# GyroCam_BNO055_v2.net
KiCad netlist of a schematic drawn in EAGLE
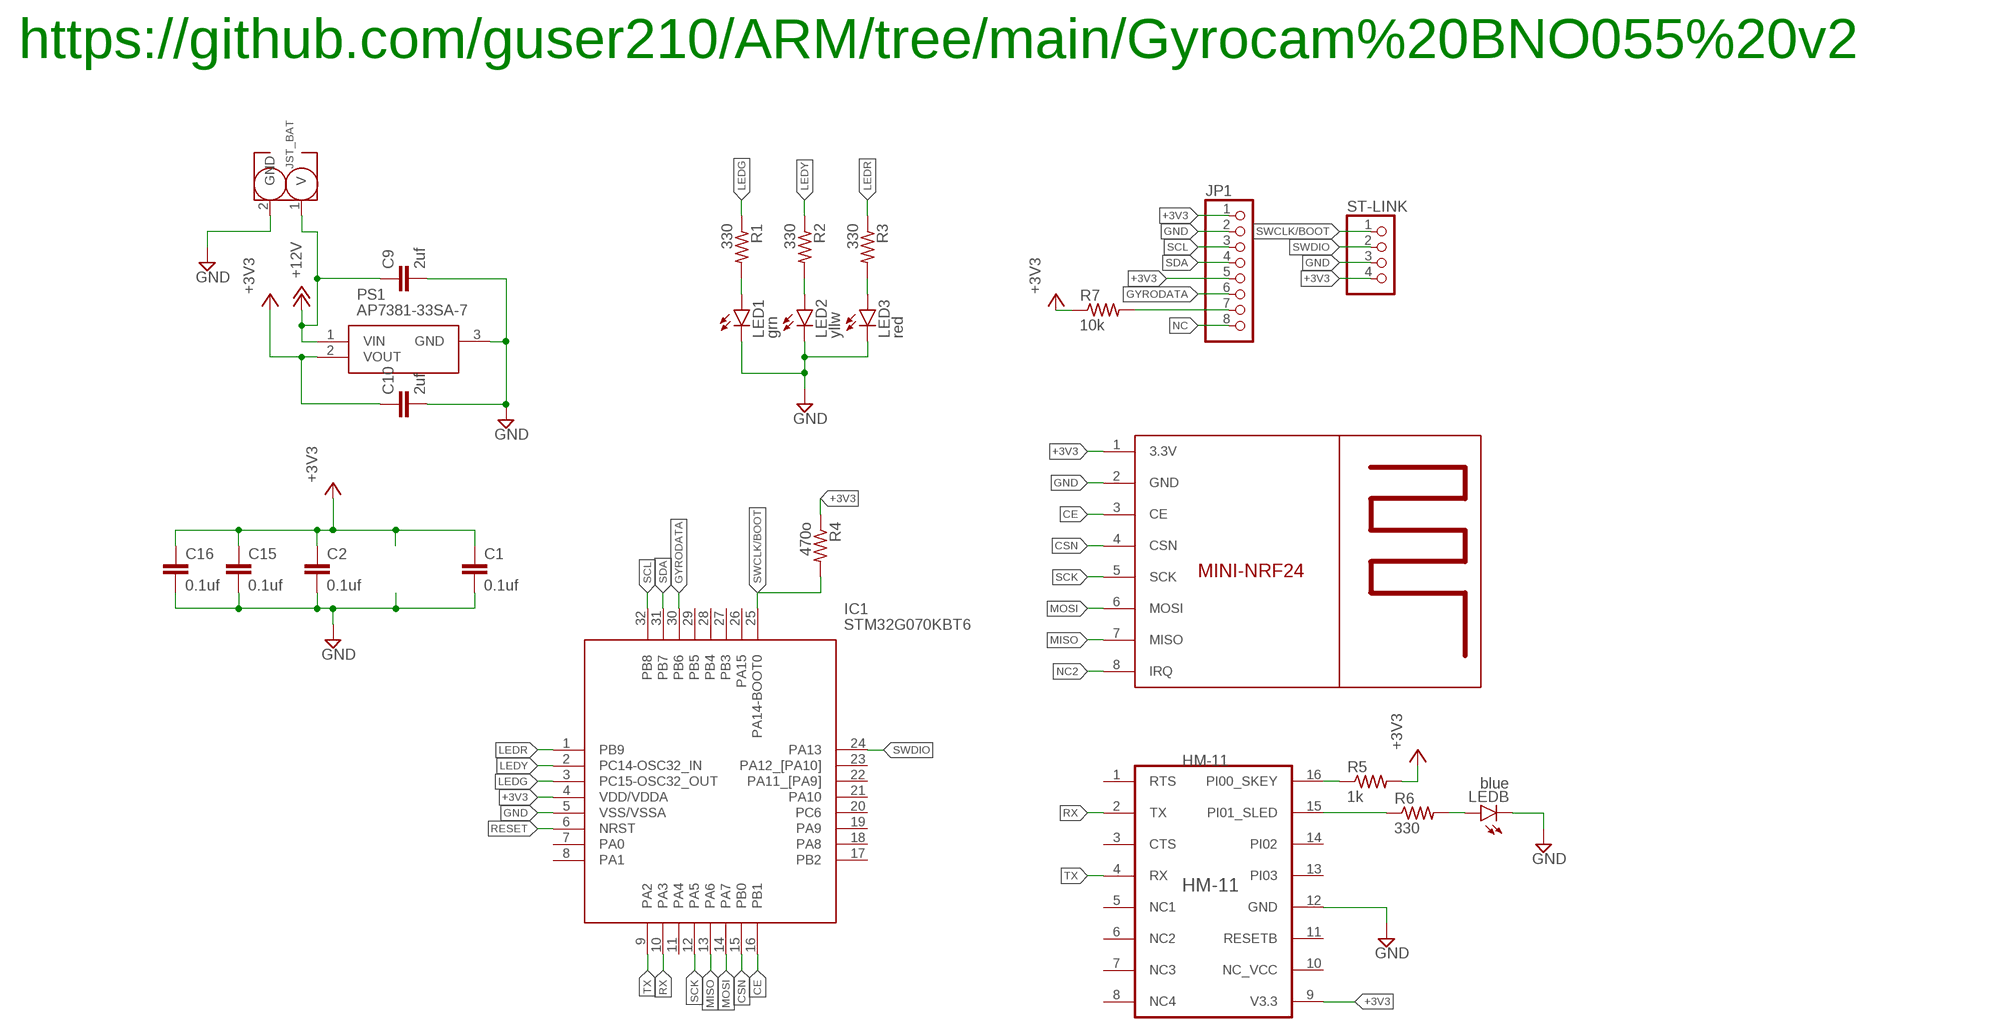
[diagram p0: schematic, sheet 1]

(export (version "E")
  (design (tool "Eeschema 10.0.6"))
  (components
    (comp (ref "C1")
      (value "0.1uf")
      (footprint "eagle-import:C0603K")
      (libsource (lib "eagle-import") (part "C-EUC0603K"))
    )
    (comp (ref "C2")
      (value "0.1uf")
      (footprint "eagle-import:C0805K")
      (libsource (lib "eagle-import") (part "C-EUC0805K"))
    )
    (comp (ref "C9")
      (value "2uf")
      (footprint "eagle-import:C0805K")
      (libsource (lib "eagle-import") (part "C-EUC0805K"))
    )
    (comp (ref "C10")
      (value "2uf")
      (footprint "eagle-import:C0805K")
      (libsource (lib "eagle-import") (part "C-EUC0805K"))
    )
    (comp (ref "C15")
      (value "0.1uf")
      (footprint "eagle-import:C0805K")
      (libsource (lib "eagle-import") (part "C-EUC0805K"))
    )
    (comp (ref "C16")
      (value "0.1uf")
      (footprint "eagle-import:C0805K")
      (libsource (lib "eagle-import") (part "C-EUC0805K"))
    )
    (comp (ref "IC1")
      (value "STM32G070KBT6")
      (footprint "eagle-import:QFP80P900X900X160-32N")
      (fields (field (name "MOUSER_PART_NUMBER") "511-STM32G070KBT6"))
      (libsource (lib "eagle-import") (part "STM32G070KBT6"))
    )
    (comp (ref "JP1")
      (value "PINHD-1X8")
      (footprint "eagle-import:1X08")
      (libsource (lib "eagle-import") (part "PINHD-1X8"))
    )
    (comp (ref "LED1")
      (value "grn")
      (footprint "eagle-import:SML0805")
      (libsource (lib "eagle-import") (part "LEDSML0805"))
    )
    (comp (ref "LED2")
      (value "yllw")
      (footprint "eagle-import:SML0805")
      (libsource (lib "eagle-import") (part "LEDSML0805"))
    )
    (comp (ref "LED3")
      (value "red")
      (footprint "eagle-import:SML0805")
      (libsource (lib "eagle-import") (part "LEDSML0805"))
    )
    (comp (ref "LEDB")
      (value "blue")
      (footprint "eagle-import:SML0805")
      (libsource (lib "eagle-import") (part "LEDSML0805"))
    )
    (comp (ref "PS1")
      (value "AP7381-33SA-7")
      (footprint "eagle-import:SOT96P240X120-3N")
      (fields (field (name "MOUSER_PART_NUMBER") "621-AP7381-33SA-7"))
      (libsource (lib "eagle-import") (part "AP7381-33SA-7"))
    )
    (comp (ref "R1")
      (value "330")
      (footprint "eagle-import:M0805")
      (libsource (lib "eagle-import") (part "R-US_M0805"))
    )
    (comp (ref "R2")
      (value "330")
      (footprint "eagle-import:M0805")
      (libsource (lib "eagle-import") (part "R-US_M0805"))
    )
    (comp (ref "R3")
      (value "330")
      (footprint "eagle-import:M0805")
      (libsource (lib "eagle-import") (part "R-US_M0805"))
    )
    (comp (ref "R4")
      (value "470o")
      (footprint "eagle-import:M0805")
      (libsource (lib "eagle-import") (part "R-US_M0805"))
    )
    (comp (ref "R5")
      (value "1k")
      (footprint "eagle-import:M0805")
      (libsource (lib "eagle-import") (part "R-US_M0805"))
    )
    (comp (ref "R6")
      (value "330")
      (footprint "eagle-import:M0805")
      (libsource (lib "eagle-import") (part "R-US_M0805"))
    )
    (comp (ref "R7")
      (value "10k")
      (footprint "eagle-import:M0805")
      (libsource (lib "eagle-import") (part "R-US_M0805"))
    )
    (comp (ref "ST-LINK")
      (value "PINHD-1X4")
      (footprint "eagle-import:1X04")
      (libsource (lib "eagle-import") (part "PINHD-1X4"))
    )
    (comp (ref "SUPP")
      (value "JST2.0MM_2PIN")
      (footprint "eagle-import:JST2.0MM_2PIN")
      (libsource (lib "eagle-import") (part "JST2.0MM_2PIN"))
    )
    (comp (ref "U$1")
      (value "HM-11")
      (footprint "eagle-import:HM-11")
      (libsource (lib "eagle-import") (part "HM-11"))
    )
    (comp (ref "U$3")
      (value "NRF24")
      (footprint "eagle-import:NRF24L01_SMD")
      (libsource (lib "eagle-import") (part "MINI-NRF24L01PSMD"))
    )
  )
  (nets
    (net (code "1") (name "+3V3") (class "Default")
      (node (ref "C1") (pin "1") (pinfunction "1_1") (pintype "passive"))
      (node (ref "C10") (pin "1") (pinfunction "1_1") (pintype "passive"))
      (node (ref "C15") (pin "1") (pinfunction "1_1") (pintype "passive"))
      (node (ref "C16") (pin "1") (pinfunction "1_1") (pintype "passive"))
      (node (ref "C2") (pin "1") (pinfunction "1_1") (pintype "passive"))
      (node (ref "IC1") (pin "4") (pinfunction "VDD/VDDA_4") (pintype "power_in"))
      (node (ref "JP1") (pin "1") (pinfunction "1_1") (pintype "passive"))
      (node (ref "JP1") (pin "5") (pinfunction "5_5") (pintype "passive"))
      (node (ref "PS1") (pin "2") (pinfunction "VOUT_2") (pintype "bidirectional"))
      (node (ref "R4") (pin "1") (pinfunction "1_1") (pintype "passive"))
      (node (ref "R5") (pin "2") (pinfunction "2_2") (pintype "passive"))
      (node (ref "R7") (pin "1") (pinfunction "1_1") (pintype "passive"))
      (node (ref "ST-LINK") (pin "4") (pinfunction "4_4") (pintype "passive"))
      (node (ref "U$1") (pin "9") (pinfunction "V3.3_9") (pintype "bidirectional"))
      (node (ref "U$3") (pin "1") (pinfunction "3.3V_1") (pintype "bidirectional"))
    )
    (net (code "2") (name "+12V") (class "Default")
      (node (ref "C9") (pin "1") (pinfunction "1_1") (pintype "passive"))
      (node (ref "PS1") (pin "1") (pinfunction "VIN_1") (pintype "bidirectional"))
      (node (ref "SUPP") (pin "1") (pinfunction "V_1") (pintype "power_in"))
    )
    (net (code "3") (name "CE") (class "Default")
      (node (ref "IC1") (pin "16") (pinfunction "PB1_16") (pintype "bidirectional"))
      (node (ref "U$3") (pin "3") (pinfunction "CE_3") (pintype "bidirectional"))
    )
    (net (code "4") (name "CSN") (class "Default")
      (node (ref "IC1") (pin "15") (pinfunction "PB0_15") (pintype "bidirectional"))
      (node (ref "U$3") (pin "4") (pinfunction "CSN_4") (pintype "bidirectional"))
    )
    (net (code "5") (name "GND") (class "Default")
      (node (ref "C1") (pin "2") (pinfunction "2_2") (pintype "passive"))
      (node (ref "C10") (pin "2") (pinfunction "2_2") (pintype "passive"))
      (node (ref "C15") (pin "2") (pinfunction "2_2") (pintype "passive"))
      (node (ref "C16") (pin "2") (pinfunction "2_2") (pintype "passive"))
      (node (ref "C2") (pin "2") (pinfunction "2_2") (pintype "passive"))
      (node (ref "C9") (pin "2") (pinfunction "2_2") (pintype "passive"))
      (node (ref "IC1") (pin "5") (pinfunction "VSS/VSSA_5") (pintype "power_in"))
      (node (ref "JP1") (pin "2") (pinfunction "2_2") (pintype "passive"))
      (node (ref "LED1") (pin "C") (pinfunction "C_C") (pintype "passive"))
      (node (ref "LED2") (pin "C") (pinfunction "C_C") (pintype "passive"))
      (node (ref "LED3") (pin "C") (pinfunction "C_C") (pintype "passive"))
      (node (ref "LEDB") (pin "C") (pinfunction "C_C") (pintype "passive"))
      (node (ref "PS1") (pin "3") (pinfunction "GND_3") (pintype "bidirectional"))
      (node (ref "ST-LINK") (pin "3") (pinfunction "3_3") (pintype "passive"))
      (node (ref "SUPP") (pin "2") (pinfunction "GND_2") (pintype "power_in"))
      (node (ref "U$1") (pin "12") (pinfunction "GND_12") (pintype "bidirectional"))
      (node (ref "U$3") (pin "2") (pinfunction "GND_2") (pintype "bidirectional"))
    )
    (net (code "6") (name "GYRODATA") (class "Default")
      (node (ref "IC1") (pin "30") (pinfunction "PB6_30") (pintype "bidirectional"))
      (node (ref "JP1") (pin "6") (pinfunction "6_6") (pintype "passive"))
    )
    (net (code "7") (name "LEDG") (class "Default")
      (node (ref "IC1") (pin "3") (pinfunction "PC15-OSC32_OUT_3") (pintype "bidirectional"))
      (node (ref "R1") (pin "1") (pinfunction "1_1") (pintype "passive"))
    )
    (net (code "8") (name "LEDR") (class "Default")
      (node (ref "IC1") (pin "1") (pinfunction "PB9_1") (pintype "bidirectional"))
      (node (ref "R3") (pin "1") (pinfunction "1_1") (pintype "passive"))
    )
    (net (code "9") (name "LEDY") (class "Default")
      (node (ref "IC1") (pin "2") (pinfunction "PC14-OSC32_IN_2") (pintype "bidirectional"))
      (node (ref "R2") (pin "1") (pinfunction "1_1") (pintype "passive"))
    )
    (net (code "10") (name "MISO") (class "Default")
      (node (ref "IC1") (pin "13") (pinfunction "PA6_13") (pintype "bidirectional"))
      (node (ref "U$3") (pin "7") (pinfunction "MISO_7") (pintype "bidirectional"))
    )
    (net (code "11") (name "MOSI") (class "Default")
      (node (ref "IC1") (pin "14") (pinfunction "PA7_14") (pintype "bidirectional"))
      (node (ref "U$3") (pin "6") (pinfunction "MOSI_6") (pintype "bidirectional"))
    )
    (net (code "12") (name "NC") (class "Default")
      (node (ref "JP1") (pin "8") (pinfunction "8_8") (pintype "passive"))
    )
    (net (code "13") (name "NC2") (class "Default")
      (node (ref "U$3") (pin "8") (pinfunction "IRQ_8") (pintype "bidirectional"))
    )
    (net (code "14") (name "Net-(JP1-Pad7)") (class "Default")
      (node (ref "JP1") (pin "7") (pinfunction "7_7") (pintype "passive"))
      (node (ref "R7") (pin "2") (pinfunction "2_2") (pintype "passive"))
    )
    (net (code "15") (name "Net-(LED1-PadA)") (class "Default")
      (node (ref "LED1") (pin "A") (pinfunction "A_A") (pintype "passive"))
      (node (ref "R1") (pin "2") (pinfunction "2_2") (pintype "passive"))
    )
    (net (code "16") (name "Net-(LED2-PadA)") (class "Default")
      (node (ref "LED2") (pin "A") (pinfunction "A_A") (pintype "passive"))
      (node (ref "R2") (pin "2") (pinfunction "2_2") (pintype "passive"))
    )
    (net (code "17") (name "Net-(LED3-PadA)") (class "Default")
      (node (ref "LED3") (pin "A") (pinfunction "A_A") (pintype "passive"))
      (node (ref "R3") (pin "2") (pinfunction "2_2") (pintype "passive"))
    )
    (net (code "18") (name "Net-(LEDB-PadA)") (class "Default")
      (node (ref "LEDB") (pin "A") (pinfunction "A_A") (pintype "passive"))
      (node (ref "R6") (pin "2") (pinfunction "2_2") (pintype "passive"))
    )
    (net (code "19") (name "Net-(U$1-PI00_SKEY)") (class "Default")
      (node (ref "R5") (pin "1") (pinfunction "1_1") (pintype "passive"))
      (node (ref "U$1") (pin "16") (pinfunction "PI00_SKEY_16") (pintype "bidirectional"))
    )
    (net (code "20") (name "Net-(U$1-PI01_SLED)") (class "Default")
      (node (ref "R6") (pin "1") (pinfunction "1_1") (pintype "passive"))
      (node (ref "U$1") (pin "15") (pinfunction "PI01_SLED_15") (pintype "bidirectional"))
    )
    (net (code "21") (name "RESET") (class "Default")
      (node (ref "IC1") (pin "6") (pinfunction "NRST_6") (pintype "bidirectional"))
    )
    (net (code "22") (name "RX") (class "Default")
      (node (ref "IC1") (pin "10") (pinfunction "PA3_10") (pintype "bidirectional"))
      (node (ref "U$1") (pin "2") (pinfunction "TX_2") (pintype "bidirectional"))
    )
    (net (code "23") (name "SCK") (class "Default")
      (node (ref "IC1") (pin "12") (pinfunction "PA5_12") (pintype "bidirectional"))
      (node (ref "U$3") (pin "5") (pinfunction "SCK_5") (pintype "bidirectional"))
    )
    (net (code "24") (name "SCL") (class "Default")
      (node (ref "IC1") (pin "32") (pinfunction "PB8_32") (pintype "bidirectional"))
      (node (ref "JP1") (pin "3") (pinfunction "3_3") (pintype "passive"))
    )
    (net (code "25") (name "SDA") (class "Default")
      (node (ref "IC1") (pin "31") (pinfunction "PB7_31") (pintype "bidirectional"))
      (node (ref "JP1") (pin "4") (pinfunction "4_4") (pintype "passive"))
    )
    (net (code "26") (name "SWCLK{slash}BOOT") (class "Default")
      (node (ref "IC1") (pin "25") (pinfunction "PA14-BOOT0_25") (pintype "bidirectional"))
      (node (ref "R4") (pin "2") (pinfunction "2_2") (pintype "passive"))
      (node (ref "ST-LINK") (pin "1") (pinfunction "1_1") (pintype "passive"))
    )
    (net (code "27") (name "SWDIO") (class "Default")
      (node (ref "IC1") (pin "24") (pinfunction "PA13_24") (pintype "bidirectional"))
      (node (ref "ST-LINK") (pin "2") (pinfunction "2_2") (pintype "passive"))
    )
    (net (code "28") (name "TX") (class "Default")
      (node (ref "IC1") (pin "9") (pinfunction "PA2_9") (pintype "bidirectional"))
      (node (ref "U$1") (pin "4") (pinfunction "RX_4") (pintype "bidirectional"))
    )
    (net (code "29") (name "unconnected-(IC1-PA0-Pad7)") (class "Default")
      (node (ref "IC1") (pin "7") (pinfunction "PA0_7") (pintype "bidirectional"))
    )
    (net (code "30") (name "unconnected-(IC1-PA1-Pad8)") (class "Default")
      (node (ref "IC1") (pin "8") (pinfunction "PA1_8") (pintype "bidirectional"))
    )
    (net (code "31") (name "unconnected-(IC1-PA4-Pad11)") (class "Default")
      (node (ref "IC1") (pin "11") (pinfunction "PA4_11") (pintype "bidirectional"))
    )
    (net (code "32") (name "unconnected-(IC1-PA8-Pad18)") (class "Default")
      (node (ref "IC1") (pin "18") (pinfunction "PA8_18") (pintype "bidirectional"))
    )
    (net (code "33") (name "unconnected-(IC1-PA9-Pad19)") (class "Default")
      (node (ref "IC1") (pin "19") (pinfunction "PA9_19") (pintype "bidirectional"))
    )
    (net (code "34") (name "unconnected-(IC1-PA10-Pad21)") (class "Default")
      (node (ref "IC1") (pin "21") (pinfunction "PA10_21") (pintype "bidirectional"))
    )
    (net (code "35") (name "unconnected-(IC1-PA11_[PA9]-Pad22)") (class "Default")
      (node (ref "IC1") (pin "22") (pinfunction "PA11_[PA9]_22") (pintype "bidirectional"))
    )
    (net (code "36") (name "unconnected-(IC1-PA12_[PA10]-Pad23)") (class "Default")
      (node (ref "IC1") (pin "23") (pinfunction "PA12_[PA10]_23") (pintype "bidirectional"))
    )
    (net (code "37") (name "unconnected-(IC1-PA15-Pad26)") (class "Default")
      (node (ref "IC1") (pin "26") (pinfunction "PA15_26") (pintype "bidirectional"))
    )
    (net (code "38") (name "unconnected-(IC1-PB2-Pad17)") (class "Default")
      (node (ref "IC1") (pin "17") (pinfunction "PB2_17") (pintype "bidirectional"))
    )
    (net (code "39") (name "unconnected-(IC1-PB3-Pad27)") (class "Default")
      (node (ref "IC1") (pin "27") (pinfunction "PB3_27") (pintype "bidirectional"))
    )
    (net (code "40") (name "unconnected-(IC1-PB4-Pad28)") (class "Default")
      (node (ref "IC1") (pin "28") (pinfunction "PB4_28") (pintype "bidirectional"))
    )
    (net (code "41") (name "unconnected-(IC1-PB5-Pad29)") (class "Default")
      (node (ref "IC1") (pin "29") (pinfunction "PB5_29") (pintype "bidirectional"))
    )
    (net (code "42") (name "unconnected-(IC1-PC6-Pad20)") (class "Default")
      (node (ref "IC1") (pin "20") (pinfunction "PC6_20") (pintype "bidirectional"))
    )
    (net (code "43") (name "unconnected-(U$1-CTS-Pad3)") (class "Default")
      (node (ref "U$1") (pin "3") (pinfunction "CTS_3") (pintype "bidirectional"))
    )
    (net (code "44") (name "unconnected-(U$1-NC1-Pad5)") (class "Default")
      (node (ref "U$1") (pin "5") (pinfunction "NC1_5") (pintype "bidirectional"))
    )
    (net (code "45") (name "unconnected-(U$1-NC2-Pad6)") (class "Default")
      (node (ref "U$1") (pin "6") (pinfunction "NC2_6") (pintype "bidirectional"))
    )
    (net (code "46") (name "unconnected-(U$1-NC3-Pad7)") (class "Default")
      (node (ref "U$1") (pin "7") (pinfunction "NC3_7") (pintype "bidirectional"))
    )
    (net (code "47") (name "unconnected-(U$1-NC4-Pad8)") (class "Default")
      (node (ref "U$1") (pin "8") (pinfunction "NC4_8") (pintype "bidirectional"))
    )
    (net (code "48") (name "unconnected-(U$1-NC_VCC-Pad10)") (class "Default")
      (node (ref "U$1") (pin "10") (pinfunction "NC_VCC_10") (pintype "bidirectional"))
    )
    (net (code "49") (name "unconnected-(U$1-PI02-Pad14)") (class "Default")
      (node (ref "U$1") (pin "14") (pinfunction "PI02_14") (pintype "bidirectional"))
    )
    (net (code "50") (name "unconnected-(U$1-PI03-Pad13)") (class "Default")
      (node (ref "U$1") (pin "13") (pinfunction "PI03_13") (pintype "bidirectional"))
    )
    (net (code "51") (name "unconnected-(U$1-RESETB-Pad11)") (class "Default")
      (node (ref "U$1") (pin "11") (pinfunction "RESETB_11") (pintype "bidirectional"))
    )
    (net (code "52") (name "unconnected-(U$1-RTS-Pad1)") (class "Default")
      (node (ref "U$1") (pin "1") (pinfunction "RTS_1") (pintype "bidirectional"))
    )
  )
)
